# rapidshark-half-assed-half-h-bridge-mk-1.net
KiCad netlist of a schematic drawn in EAGLE
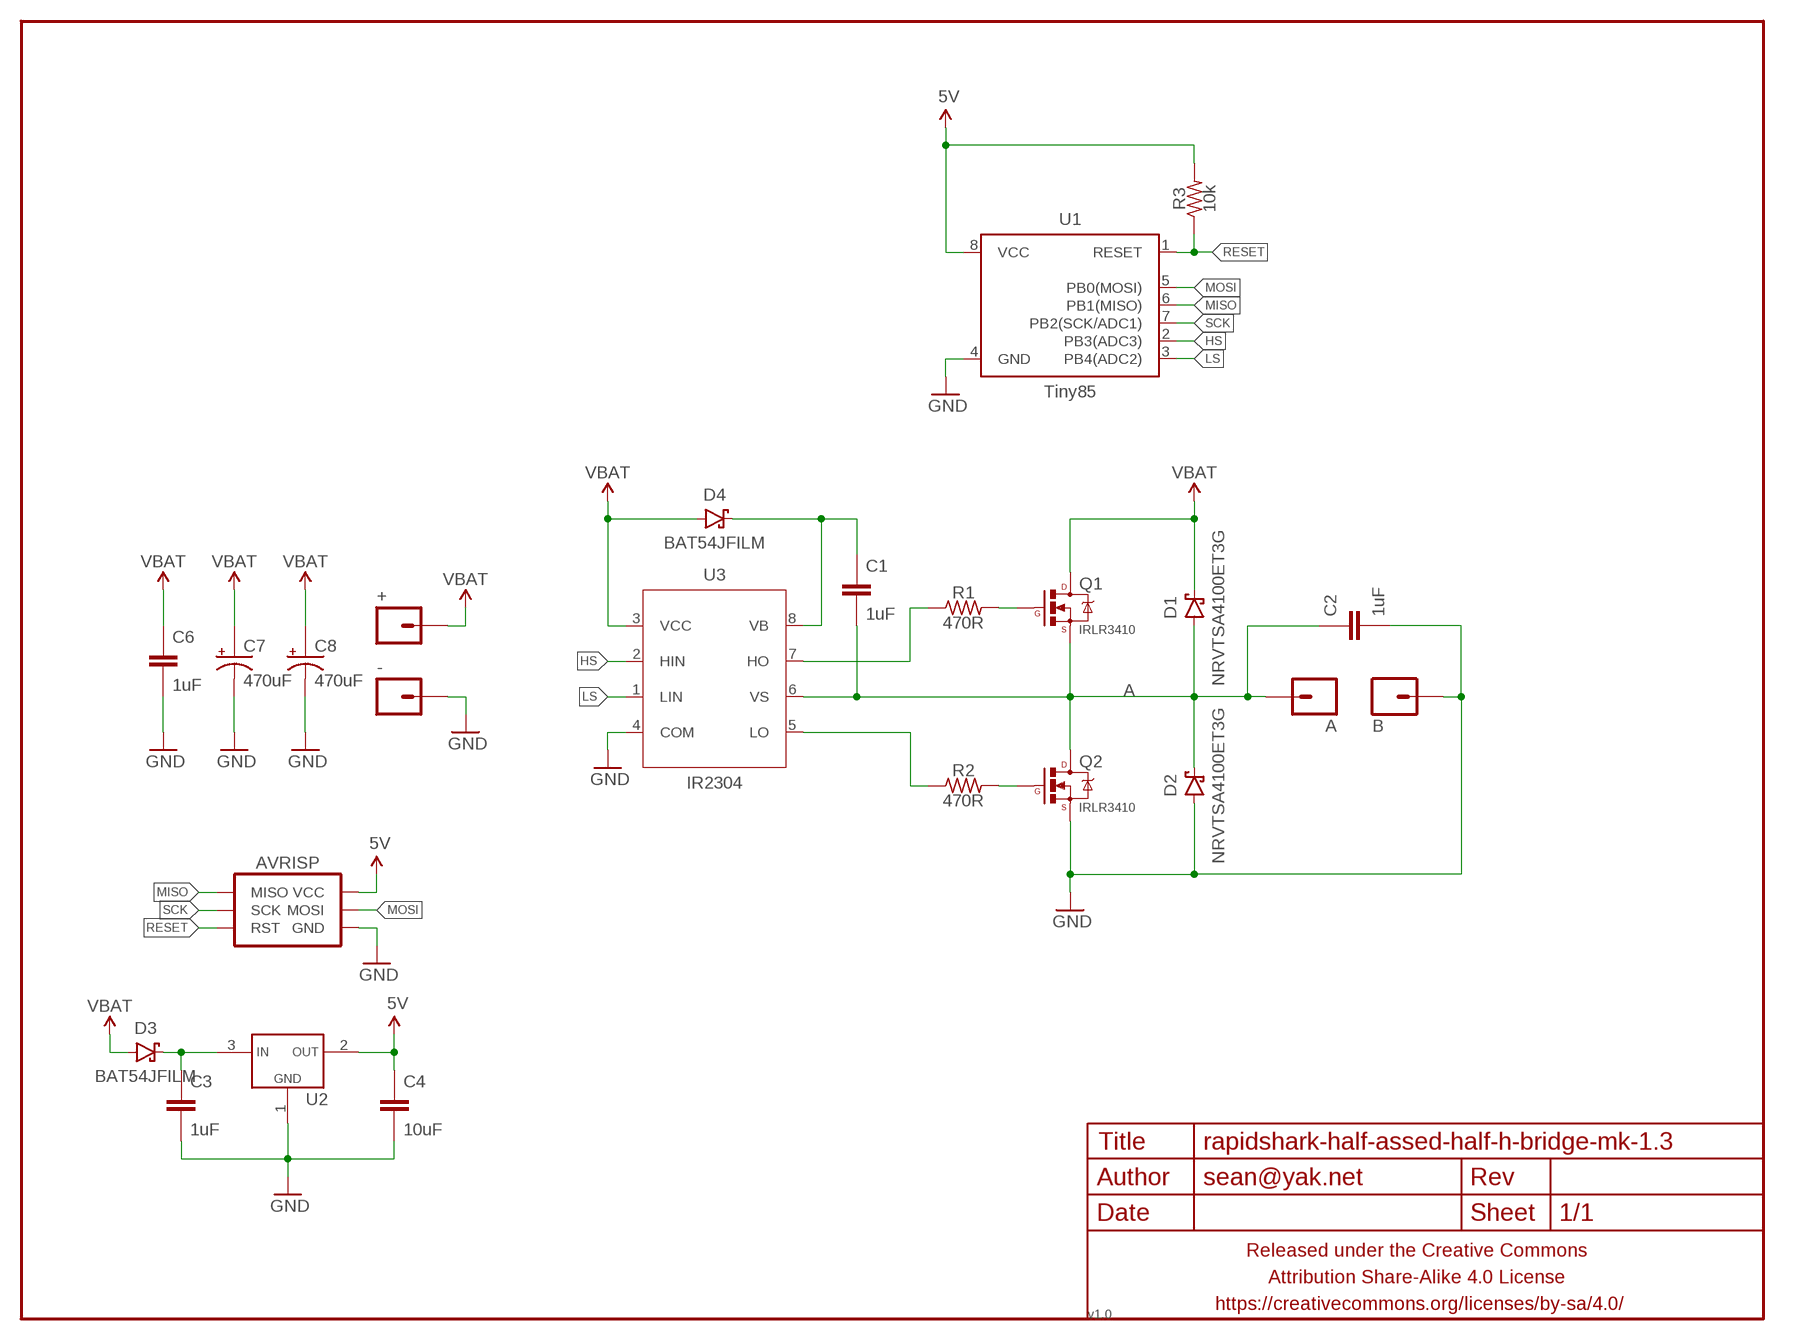
[diagram p0: schematic, sheet 1]

(export (version "E")
  (design (tool "Eeschema 10.0.6"))
  (components
    (comp (ref "+")
      (value "M01PTH-1.4MM")
      (footprint "eagle-import:1X01-1.4MM-CIR")
      (libsource (lib "eagle-import") (part "M01PTH-1.4MM"))
    )
    (comp (ref "-")
      (value "M01PTH-1.4MM")
      (footprint "eagle-import:1X01-1.4MM-CIR")
      (libsource (lib "eagle-import") (part "M01PTH-1.4MM"))
    )
    (comp (ref "A")
      (value "M01PTH-1.4MM")
      (footprint "eagle-import:1X01-1.4MM-CIR")
      (libsource (lib "eagle-import") (part "M01PTH-1.4MM"))
    )
    (comp (ref "AVRISP")
      (value "AVR_SPI_PRG_6INLINE")
      (footprint "eagle-import:AVR_MINI_PROG")
      (libsource (lib "eagle-import") (part "AVR_SPI_PRG_6INLINE"))
    )
    (comp (ref "B")
      (value "M01PTH-1.4MM")
      (footprint "eagle-import:1X01-1.4MM-CIR")
      (libsource (lib "eagle-import") (part "M01PTH-1.4MM"))
    )
    (comp (ref "C1")
      (value "1uF")
      (footprint "eagle-import:C0603-TIGHTER")
      (libsource (lib "eagle-import") (part "CAPACITOR-CERAMICC0603-TIGHTER"))
    )
    (comp (ref "C2")
      (value "1uF")
      (footprint "eagle-import:C0603-TIGHTER")
      (libsource (lib "eagle-import") (part "CAPACITOR-CERAMICC0603-TIGHTER"))
    )
    (comp (ref "C3")
      (value "1uF")
      (footprint "eagle-import:C0603-TIGHTER")
      (libsource (lib "eagle-import") (part "CAPACITOR-CERAMICC0603-TIGHTER"))
    )
    (comp (ref "C4")
      (value "10uF")
      (footprint "eagle-import:C0805-TIGHTER")
      (libsource (lib "eagle-import") (part "CAPACITOR-CERAMICC0805-TIGHTER"))
    )
    (comp (ref "C6")
      (value "1uF")
      (footprint "eagle-import:C0603-TIGHTER")
      (libsource (lib "eagle-import") (part "CAPACITOR-CERAMICC0603-TIGHTER"))
    )
    (comp (ref "C7")
      (value "470uF")
      (footprint "eagle-import:E5-10,5")
      (libsource (lib "eagle-import") (part "CAPACITOR-POLARIZEDE5-10.5"))
    )
    (comp (ref "C8")
      (value "470uF")
      (footprint "eagle-import:E5-10,5")
      (libsource (lib "eagle-import") (part "CAPACITOR-POLARIZEDE5-10.5"))
    )
    (comp (ref "D1")
      (value "NRVTSA4100ET3G")
      (footprint "eagle-import:SMA-DIODE-SCHOTTKY")
      (libsource (lib "eagle-import") (part "DIODE-SCHOTTKYSMA"))
    )
    (comp (ref "D2")
      (value "NRVTSA4100ET3G")
      (footprint "eagle-import:SMA-DIODE-SCHOTTKY")
      (libsource (lib "eagle-import") (part "DIODE-SCHOTTKYSMA"))
    )
    (comp (ref "D3")
      (value "BAT54JFILM")
      (footprint "eagle-import:SOD323-SCHOTTKY")
      (libsource (lib "eagle-import") (part "DIODE-SCHOTTKYSOD323"))
    )
    (comp (ref "D4")
      (value "BAT54JFILM")
      (footprint "eagle-import:SOD323-SCHOTTKY")
      (libsource (lib "eagle-import") (part "DIODE-SCHOTTKYSOD323"))
    )
    (comp (ref "FRAME1")
      (value "FRAME-LETTERNO_PACKAGE")
      (footprint "eagle-import:DUMMY")
      (fields
        (field (name "VERSION") "v01")
        (field (name "DESIGNER") "sean@yak.net")
        (field (name "VERSION_1") "v1.0")
      )
      (libsource (lib "eagle-import") (part "FRAME-LETTERNO_PACKAGE"))
    )
    (comp (ref "Q1")
      (value "IRLR3410")
      (footprint "eagle-import:DPAK")
      (libsource (lib "eagle-import") (part "MOSFET-NCHANNELFDD8780"))
    )
    (comp (ref "Q2")
      (value "IRLR3410")
      (footprint "eagle-import:DPAK")
      (libsource (lib "eagle-import") (part "MOSFET-NCHANNELFDD8780"))
    )
    (comp (ref "R1")
      (value "470R")
      (footprint "eagle-import:R0603-TIGHTER")
      (libsource (lib "eagle-import") (part "RESISTORR0603-TIGHTER"))
    )
    (comp (ref "R2")
      (value "470R")
      (footprint "eagle-import:R0603-TIGHTER")
      (libsource (lib "eagle-import") (part "RESISTORR0603-TIGHTER"))
    )
    (comp (ref "R3")
      (value "10k")
      (footprint "eagle-import:R0603-TIGHTER")
      (libsource (lib "eagle-import") (part "RESISTORR0603-TIGHTER"))
    )
    (comp (ref "U1")
      (value "Tiny85")
      (footprint "eagle-import:SO08-EIAJ")
      (libsource (lib "eagle-import") (part "ATTINY45TINY85-20-SOICW"))
    )
    (comp (ref "U2")
      (value "VREG_1117SOT-23")
      (footprint "eagle-import:SOT23")
      (libsource (lib "eagle-import") (part "VREG_1117SOT-23"))
    )
    (comp (ref "U3")
      (value "IR2304")
      (footprint "eagle-import:SO08")
      (libsource (lib "eagle-import") (part "IR2304SSOIC"))
    )
  )
  (nets
    (net (code "1") (name "/A") (class "Default")
      (node (ref "A") (pin "P$1") (pinfunction "1_P$1") (pintype "passive"))
      (node (ref "C1") (pin "2") (pinfunction "2_2") (pintype "passive"))
      (node (ref "C2") (pin "1") (pinfunction "1_1") (pintype "passive"))
      (node (ref "D1") (pin "A") (pinfunction "A_A") (pintype "passive"))
      (node (ref "D2") (pin "C") (pinfunction "C_C") (pintype "passive"))
      (node (ref "Q1") (pin "3") (pinfunction "S_3") (pintype "passive"))
      (node (ref "Q2") (pin "4") (pinfunction "D_4") (pintype "passive"))
      (node (ref "U3") (pin "6") (pinfunction "VS_6") (pintype "passive"))
    )
    (net (code "2") (name "5V") (class "Default")
      (node (ref "AVRISP") (pin "2") (pinfunction "VCC_2") (pintype "passive"))
      (node (ref "C4") (pin "1") (pinfunction "1_1") (pintype "passive"))
      (node (ref "R3") (pin "2") (pinfunction "2_2") (pintype "passive"))
      (node (ref "U1") (pin "8") (pinfunction "VCC_8") (pintype "bidirectional"))
      (node (ref "U2") (pin "2") (pinfunction "VOUT_2") (pintype "bidirectional"))
    )
    (net (code "3") (name "GND") (class "Default")
      (node (ref "-") (pin "P$1") (pinfunction "1_P$1") (pintype "passive"))
      (node (ref "AVRISP") (pin "6") (pinfunction "GND_6") (pintype "passive"))
      (node (ref "B") (pin "P$1") (pinfunction "1_P$1") (pintype "passive"))
      (node (ref "C2") (pin "2") (pinfunction "2_2") (pintype "passive"))
      (node (ref "C3") (pin "2") (pinfunction "2_2") (pintype "passive"))
      (node (ref "C4") (pin "2") (pinfunction "2_2") (pintype "passive"))
      (node (ref "C6") (pin "2") (pinfunction "2_2") (pintype "passive"))
      (node (ref "C7") (pin "-") (pinfunction "-_-") (pintype "passive"))
      (node (ref "C8") (pin "-") (pinfunction "-_-") (pintype "passive"))
      (node (ref "D2") (pin "A") (pinfunction "A_A") (pintype "passive"))
      (node (ref "Q2") (pin "3") (pinfunction "S_3") (pintype "passive"))
      (node (ref "U1") (pin "4") (pinfunction "GND_4") (pintype "bidirectional"))
      (node (ref "U2") (pin "1") (pinfunction "GND_1") (pintype "bidirectional"))
      (node (ref "U3") (pin "4") (pinfunction "COM_4") (pintype "passive"))
    )
    (net (code "4") (name "HS") (class "Default")
      (node (ref "U1") (pin "2") (pinfunction "PB3(ADC3)_2") (pintype "bidirectional"))
      (node (ref "U3") (pin "2") (pinfunction "HIN_2") (pintype "passive"))
    )
    (net (code "5") (name "LS") (class "Default")
      (node (ref "U1") (pin "3") (pinfunction "PB4(ADC2)_3") (pintype "bidirectional"))
      (node (ref "U3") (pin "1") (pinfunction "LIN_1") (pintype "passive"))
    )
    (net (code "6") (name "MISO") (class "Default")
      (node (ref "AVRISP") (pin "1") (pinfunction "MISO_1") (pintype "passive"))
      (node (ref "U1") (pin "6") (pinfunction "PB1(MISO)_6") (pintype "bidirectional"))
    )
    (net (code "7") (name "MOSI") (class "Default")
      (node (ref "AVRISP") (pin "4") (pinfunction "MOSI_4") (pintype "passive"))
      (node (ref "U1") (pin "5") (pinfunction "PB0(MOSI)_5") (pintype "bidirectional"))
    )
    (net (code "8") (name "Net-(Q1-G)") (class "Default")
      (node (ref "Q1") (pin "1") (pinfunction "G_1") (pintype "passive"))
      (node (ref "R1") (pin "2") (pinfunction "2_2") (pintype "passive"))
    )
    (net (code "9") (name "Net-(Q2-G)") (class "Default")
      (node (ref "Q2") (pin "1") (pinfunction "G_1") (pintype "passive"))
      (node (ref "R2") (pin "2") (pinfunction "2_2") (pintype "passive"))
    )
    (net (code "10") (name "Net-(U2-VIN)") (class "Default")
      (node (ref "C3") (pin "1") (pinfunction "1_1") (pintype "passive"))
      (node (ref "D3") (pin "C") (pinfunction "C_C") (pintype "passive"))
      (node (ref "U2") (pin "3") (pinfunction "VIN_3") (pintype "bidirectional"))
    )
    (net (code "11") (name "Net-(U3-HO)") (class "Default")
      (node (ref "R1") (pin "1") (pinfunction "1_1") (pintype "passive"))
      (node (ref "U3") (pin "7") (pinfunction "HO_7") (pintype "passive"))
    )
    (net (code "12") (name "Net-(U3-LO)") (class "Default")
      (node (ref "R2") (pin "1") (pinfunction "1_1") (pintype "passive"))
      (node (ref "U3") (pin "5") (pinfunction "LO_5") (pintype "passive"))
    )
    (net (code "13") (name "Net-(U3-VB)") (class "Default")
      (node (ref "C1") (pin "1") (pinfunction "1_1") (pintype "passive"))
      (node (ref "D4") (pin "C") (pinfunction "C_C") (pintype "passive"))
      (node (ref "U3") (pin "8") (pinfunction "VB_8") (pintype "passive"))
    )
    (net (code "14") (name "RESET") (class "Default")
      (node (ref "AVRISP") (pin "5") (pinfunction "RST_5") (pintype "passive"))
      (node (ref "R3") (pin "1") (pinfunction "1_1") (pintype "passive"))
      (node (ref "U1") (pin "1") (pinfunction "RESET_1") (pintype "bidirectional"))
    )
    (net (code "15") (name "SCK") (class "Default")
      (node (ref "AVRISP") (pin "3") (pinfunction "SCK_3") (pintype "passive"))
      (node (ref "U1") (pin "7") (pinfunction "PB2(SCK/ADC1)_7") (pintype "bidirectional"))
    )
    (net (code "16") (name "VBAT") (class "Default")
      (node (ref "+") (pin "P$1") (pinfunction "1_P$1") (pintype "passive"))
      (node (ref "C6") (pin "1") (pinfunction "1_1") (pintype "passive"))
      (node (ref "C7") (pin "+") (pinfunction "+_+") (pintype "passive"))
      (node (ref "C8") (pin "+") (pinfunction "+_+") (pintype "passive"))
      (node (ref "D1") (pin "C") (pinfunction "C_C") (pintype "passive"))
      (node (ref "D3") (pin "A") (pinfunction "A_A") (pintype "passive"))
      (node (ref "D4") (pin "A") (pinfunction "A_A") (pintype "passive"))
      (node (ref "Q1") (pin "4") (pinfunction "D_4") (pintype "passive"))
      (node (ref "U3") (pin "3") (pinfunction "VCC_3") (pintype "passive"))
    )
  )
)
